# STM32.net
KiCad netlist of a schematic drawn in Altium Designer
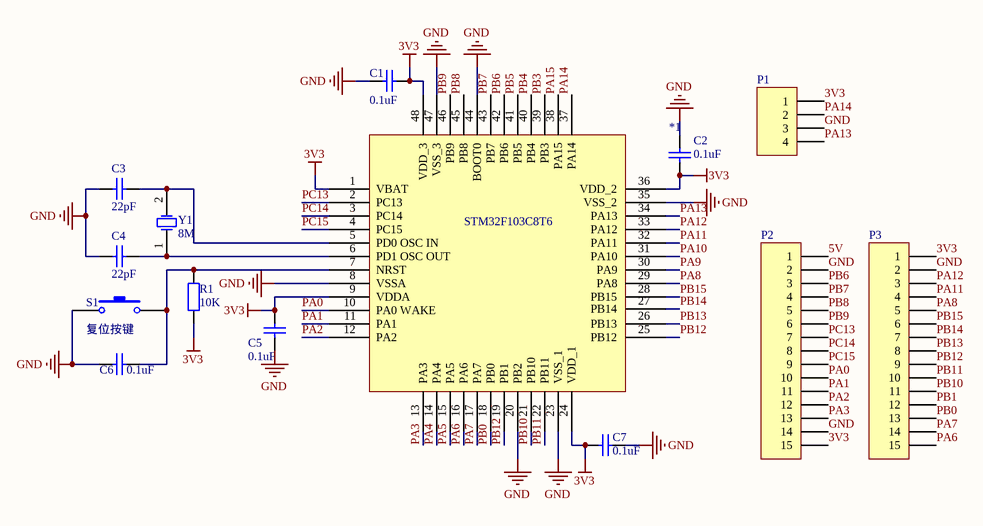
[diagram p0: STM32最小系统.SchDoc]

(export (version "E")
  (design (tool "Eeschema 10.0.6"))
  (components
    (comp (ref "*1") (value "STM32F103C8T6") (libsource (lib "ST32F103C8T6") (part "STM32F103C8T6")))
    (comp (ref "C1")
      (value "0.1uF")
      (footprint "RAD-0.3")
      (description "Capacitor")
      (fields (field (name "Comment") "Cap") (field (name "PUBLISHER") "Altium Limited"))
      (libsource (lib "Miscellaneous Devices") (part "Cap"))
    )
    (comp (ref "C2")
      (value "0.1uF")
      (footprint "RAD-0.3")
      (description "Capacitor")
      (fields (field (name "Comment") "Cap") (field (name "PUBLISHER") "Altium Limited"))
      (libsource (lib "Miscellaneous Devices") (part "Cap"))
    )
    (comp (ref "C3")
      (value "22pF")
      (footprint "RAD-0.3")
      (description "Capacitor")
      (fields (field (name "Comment") "Cap") (field (name "PUBLISHER") "Altium Limited"))
      (libsource (lib "Miscellaneous Devices") (part "Cap"))
    )
    (comp (ref "C4")
      (value "22pF")
      (footprint "RAD-0.3")
      (description "Capacitor")
      (fields (field (name "Comment") "Cap") (field (name "PUBLISHER") "Altium Limited"))
      (libsource (lib "Miscellaneous Devices") (part "Cap"))
    )
    (comp (ref "C5")
      (value "0.1uF")
      (footprint "RAD-0.3")
      (description "Capacitor")
      (fields (field (name "Comment") "Cap") (field (name "PUBLISHER") "Altium Limited"))
      (libsource (lib "Miscellaneous Devices") (part "Cap"))
    )
    (comp (ref "C6")
      (value "0.1uF")
      (footprint "RAD-0.3")
      (description "Capacitor")
      (fields (field (name "Comment") "Cap") (field (name "PUBLISHER") "Altium Limited"))
      (libsource (lib "Miscellaneous Devices") (part "Cap"))
    )
    (comp (ref "C7")
      (value "0.1uF")
      (footprint "RAD-0.3")
      (description "Capacitor")
      (fields (field (name "Comment") "Cap") (field (name "PUBLISHER") "Altium Limited"))
      (libsource (lib "Miscellaneous Devices") (part "Cap"))
    )
    (comp (ref "P1")
      (value "MHDR1X4")
      (footprint "MHDR1X4")
      (description "Header, 4-Pin")
      (fields (field (name "PUBLISHER") "Altium Limited"))
      (libsource (lib "Miscellaneous Connectors") (part "MHDR1X4"))
    )
    (comp (ref "P2")
      (value "MHDR1X15")
      (footprint "MHDR1X15")
      (description "Header, 15-Pin")
      (fields (field (name "PUBLISHER") "Altium Limited"))
      (libsource (lib "Miscellaneous Connectors") (part "MHDR1X15"))
    )
    (comp (ref "P3")
      (value "MHDR1X15")
      (footprint "MHDR1X15")
      (description "Header, 15-Pin")
      (fields (field (name "PUBLISHER") "Altium Limited"))
      (libsource (lib "Miscellaneous Connectors") (part "MHDR1X15"))
    )
    (comp (ref "R1")
      (value "10K")
      (footprint "AXIAL-0.4")
      (description "Resistor")
      (fields (field (name "Comment") "Res2") (field (name "PUBLISHER") "Altium Limited"))
      (libsource (lib "Miscellaneous Devices") (part "Res2"))
    )
    (comp (ref "S1")
      (value "复位按键")
      (footprint "SPST-2")
      (description "Switch")
      (fields (field (name "PUBLISHER") "Altium Limited"))
      (libsource (lib "Miscellaneous Devices") (part "SW-PB"))
    )
    (comp (ref "Y1")
      (value "8M")
      (footprint "R38")
      (description "Crystal Oscillator")
      (fields (field (name "PUBLISHER") "Altium Limited"))
      (libsource (lib "Miscellaneous Devices") (part "XTAL"))
    )
  )
  (nets
    (net (code "1") (name "/5V") (class "Default")
      (node (ref "P2") (pin "1") (pinfunction "1_1") (pintype "passive"))
    )
    (net (code "2") (name "/PA0") (class "Default")
      (node (ref "*1") (pin "10") (pinfunction "PA0_WAKE_10") (pintype "passive"))
      (node (ref "P2") (pin "10") (pinfunction "10_10") (pintype "passive"))
    )
    (net (code "3") (name "/PA1") (class "Default")
      (node (ref "*1") (pin "11") (pinfunction "PA1_11") (pintype "passive"))
      (node (ref "P2") (pin "11") (pinfunction "11_11") (pintype "passive"))
    )
    (net (code "4") (name "/PA2") (class "Default")
      (node (ref "*1") (pin "12") (pinfunction "PA2_12") (pintype "passive"))
      (node (ref "P2") (pin "12") (pinfunction "12_12") (pintype "passive"))
    )
    (net (code "5") (name "/PA3") (class "Default")
      (node (ref "*1") (pin "13") (pinfunction "PA3_13") (pintype "passive"))
      (node (ref "P2") (pin "13") (pinfunction "13_13") (pintype "passive"))
    )
    (net (code "6") (name "/PA4") (class "Default")
      (node (ref "*1") (pin "14") (pinfunction "PA4_14") (pintype "passive"))
    )
    (net (code "7") (name "/PA5") (class "Default")
      (node (ref "*1") (pin "15") (pinfunction "PA5_15") (pintype "passive"))
    )
    (net (code "8") (name "/PA6") (class "Default")
      (node (ref "*1") (pin "16") (pinfunction "PA6_16") (pintype "passive"))
      (node (ref "P3") (pin "15") (pinfunction "15_15") (pintype "passive"))
    )
    (net (code "9") (name "/PA7") (class "Default")
      (node (ref "*1") (pin "17") (pinfunction "PA7_17") (pintype "passive"))
      (node (ref "P3") (pin "14") (pinfunction "14_14") (pintype "passive"))
    )
    (net (code "10") (name "/PA8") (class "Default")
      (node (ref "*1") (pin "29") (pinfunction "PA8_29") (pintype "passive"))
      (node (ref "P3") (pin "5") (pinfunction "5_5") (pintype "passive"))
    )
    (net (code "11") (name "/PA9") (class "Default")
      (node (ref "*1") (pin "30") (pinfunction "PA9_30") (pintype "passive"))
    )
    (net (code "12") (name "/PA10") (class "Default")
      (node (ref "*1") (pin "31") (pinfunction "PA10_31") (pintype "passive"))
    )
    (net (code "13") (name "/PA11") (class "Default")
      (node (ref "*1") (pin "32") (pinfunction "PA11_32") (pintype "passive"))
      (node (ref "P3") (pin "4") (pinfunction "4_4") (pintype "passive"))
    )
    (net (code "14") (name "/PA12") (class "Default")
      (node (ref "*1") (pin "33") (pinfunction "PA12_33") (pintype "passive"))
      (node (ref "P3") (pin "3") (pinfunction "3_3") (pintype "passive"))
    )
    (net (code "15") (name "/PA13") (class "Default")
      (node (ref "*1") (pin "34") (pinfunction "PA13_34") (pintype "passive"))
      (node (ref "P1") (pin "4") (pinfunction "4_4") (pintype "passive"))
    )
    (net (code "16") (name "/PA14") (class "Default")
      (node (ref "*1") (pin "37") (pinfunction "PA14_37") (pintype "passive"))
      (node (ref "P1") (pin "2") (pinfunction "2_2") (pintype "passive"))
    )
    (net (code "17") (name "/PA15") (class "Default")
      (node (ref "*1") (pin "38") (pinfunction "PA15_38") (pintype "passive"))
    )
    (net (code "18") (name "/PB0") (class "Default")
      (node (ref "*1") (pin "18") (pinfunction "PB0_18") (pintype "passive"))
      (node (ref "P3") (pin "13") (pinfunction "13_13") (pintype "passive"))
    )
    (net (code "19") (name "/PB1") (class "Default")
      (node (ref "P3") (pin "12") (pinfunction "12_12") (pintype "passive"))
    )
    (net (code "20") (name "/PB3") (class "Default")
      (node (ref "*1") (pin "39") (pinfunction "PB3_39") (pintype "passive"))
    )
    (net (code "21") (name "/PB4") (class "Default")
      (node (ref "*1") (pin "40") (pinfunction "PB4_40") (pintype "passive"))
    )
    (net (code "22") (name "/PB5") (class "Default")
      (node (ref "*1") (pin "41") (pinfunction "PB5_41") (pintype "passive"))
    )
    (net (code "23") (name "/PB6") (class "Default")
      (node (ref "*1") (pin "42") (pinfunction "PB6_42") (pintype "passive"))
      (node (ref "P2") (pin "3") (pinfunction "3_3") (pintype "passive"))
    )
    (net (code "24") (name "/PB7") (class "Default")
      (node (ref "*1") (pin "43") (pinfunction "PB7_43") (pintype "passive"))
      (node (ref "P2") (pin "4") (pinfunction "4_4") (pintype "passive"))
    )
    (net (code "25") (name "/PB8") (class "Default")
      (node (ref "*1") (pin "45") (pinfunction "PB8_45") (pintype "passive"))
      (node (ref "P2") (pin "5") (pinfunction "5_5") (pintype "passive"))
    )
    (net (code "26") (name "/PB9") (class "Default")
      (node (ref "*1") (pin "46") (pinfunction "PB9_46") (pintype "passive"))
      (node (ref "P2") (pin "6") (pinfunction "6_6") (pintype "passive"))
    )
    (net (code "27") (name "/PB10") (class "Default")
      (node (ref "*1") (pin "21") (pinfunction "PB10_21") (pintype "passive"))
      (node (ref "P3") (pin "11") (pinfunction "11_11") (pintype "passive"))
    )
    (net (code "28") (name "/PB11") (class "Default")
      (node (ref "*1") (pin "22") (pinfunction "PB11_22") (pintype "passive"))
      (node (ref "P3") (pin "10") (pinfunction "10_10") (pintype "passive"))
    )
    (net (code "29") (name "/PB12") (class "Default")
      (node (ref "*1") (pin "19") (pinfunction "PB1_19") (pintype "passive"))
      (node (ref "*1") (pin "25") (pinfunction "PB12_25") (pintype "passive"))
      (node (ref "P3") (pin "9") (pinfunction "9_9") (pintype "passive"))
    )
    (net (code "30") (name "/PB13") (class "Default")
      (node (ref "*1") (pin "26") (pinfunction "PB13_26") (pintype "passive"))
      (node (ref "P3") (pin "8") (pinfunction "8_8") (pintype "passive"))
    )
    (net (code "31") (name "/PB14") (class "Default")
      (node (ref "*1") (pin "27") (pinfunction "PB14_27") (pintype "passive"))
      (node (ref "P3") (pin "7") (pinfunction "7_7") (pintype "passive"))
    )
    (net (code "32") (name "/PB15") (class "Default")
      (node (ref "*1") (pin "28") (pinfunction "PB15_28") (pintype "passive"))
      (node (ref "P3") (pin "6") (pinfunction "6_6") (pintype "passive"))
    )
    (net (code "33") (name "/PC13") (class "Default")
      (node (ref "*1") (pin "2") (pinfunction "PC13_2") (pintype "passive"))
      (node (ref "P2") (pin "7") (pinfunction "7_7") (pintype "passive"))
    )
    (net (code "34") (name "/PC14") (class "Default")
      (node (ref "*1") (pin "3") (pinfunction "PC14_3") (pintype "passive"))
      (node (ref "P2") (pin "8") (pinfunction "8_8") (pintype "passive"))
    )
    (net (code "35") (name "/PC15") (class "Default")
      (node (ref "*1") (pin "4") (pinfunction "PC15_4") (pintype "passive"))
      (node (ref "P2") (pin "9") (pinfunction "9_9") (pintype "passive"))
    )
    (net (code "36") (name "3V3") (class "Default")
      (node (ref "*1") (pin "1") (pinfunction "VBAT_1") (pintype "passive"))
      (node (ref "*1") (pin "24") (pinfunction "VDD_1_24") (pintype "passive"))
      (node (ref "*1") (pin "36") (pinfunction "VDD_2_36") (pintype "passive"))
      (node (ref "*1") (pin "48") (pinfunction "VDD_3_48") (pintype "passive"))
      (node (ref "*1") (pin "9") (pinfunction "VDDA_9") (pintype "passive"))
      (node (ref "C1") (pin "2") (pinfunction "2_2") (pintype "passive"))
      (node (ref "C2") (pin "1") (pinfunction "1_1") (pintype "passive"))
      (node (ref "C5") (pin "2") (pinfunction "2_2") (pintype "passive"))
      (node (ref "C7") (pin "1") (pinfunction "1_1") (pintype "passive"))
      (node (ref "P1") (pin "1") (pinfunction "1_1") (pintype "passive"))
      (node (ref "P2") (pin "15") (pinfunction "15_15") (pintype "passive"))
      (node (ref "P3") (pin "1") (pinfunction "1_1") (pintype "passive"))
      (node (ref "R1") (pin "1") (pinfunction "1_1") (pintype "passive"))
    )
    (net (code "37") (name "GND") (class "Default")
      (node (ref "*1") (pin "20") (pinfunction "PB2_20") (pintype "passive"))
      (node (ref "*1") (pin "23") (pinfunction "VSS_1_23") (pintype "passive"))
      (node (ref "*1") (pin "35") (pinfunction "VSS_2_35") (pintype "passive"))
      (node (ref "*1") (pin "44") (pinfunction "BOOT0_44") (pintype "passive"))
      (node (ref "*1") (pin "47") (pinfunction "VSS_3_47") (pintype "passive"))
      (node (ref "*1") (pin "8") (pinfunction "VSSA_8") (pintype "passive"))
      (node (ref "C1") (pin "1") (pinfunction "1_1") (pintype "passive"))
      (node (ref "C2") (pin "2") (pinfunction "2_2") (pintype "passive"))
      (node (ref "C3") (pin "2") (pinfunction "2_2") (pintype "passive"))
      (node (ref "C4") (pin "2") (pinfunction "2_2") (pintype "passive"))
      (node (ref "C5") (pin "1") (pinfunction "1_1") (pintype "passive"))
      (node (ref "C6") (pin "2") (pinfunction "2_2") (pintype "passive"))
      (node (ref "C7") (pin "2") (pinfunction "2_2") (pintype "passive"))
      (node (ref "P1") (pin "3") (pinfunction "3_3") (pintype "passive"))
      (node (ref "P2") (pin "14") (pinfunction "14_14") (pintype "passive"))
      (node (ref "P2") (pin "2") (pinfunction "2_2") (pintype "passive"))
      (node (ref "P3") (pin "2") (pinfunction "2_2") (pintype "passive"))
      (node (ref "S1") (pin "1") (pinfunction "1_1") (pintype "passive"))
    )
    (net (code "38") (name "Net-(*1-NRST)") (class "Default")
      (node (ref "*1") (pin "7") (pinfunction "NRST_7") (pintype "passive"))
      (node (ref "C6") (pin "1") (pinfunction "1_1") (pintype "passive"))
      (node (ref "R1") (pin "2") (pinfunction "2_2") (pintype "passive"))
      (node (ref "S1") (pin "2") (pinfunction "2_2") (pintype "passive"))
    )
    (net (code "39") (name "Net-(*1-PD0_OSC_IN)") (class "Default")
      (node (ref "*1") (pin "5") (pinfunction "PD0_OSC_IN_5") (pintype "passive"))
      (node (ref "C3") (pin "1") (pinfunction "1_1") (pintype "passive"))
      (node (ref "Y1") (pin "2") (pinfunction "OSC2_2") (pintype "passive"))
    )
    (net (code "40") (name "Net-(*1-PD1_OSC_OUT)") (class "Default")
      (node (ref "*1") (pin "6") (pinfunction "PD1_OSC_OUT_6") (pintype "passive"))
      (node (ref "C4") (pin "1") (pinfunction "1_1") (pintype "passive"))
      (node (ref "Y1") (pin "1") (pinfunction "OSC1_1") (pintype "passive"))
    )
  )
)
